# NOS_EEG_V2.net
KiCad netlist of a schematic drawn in Altium Designer
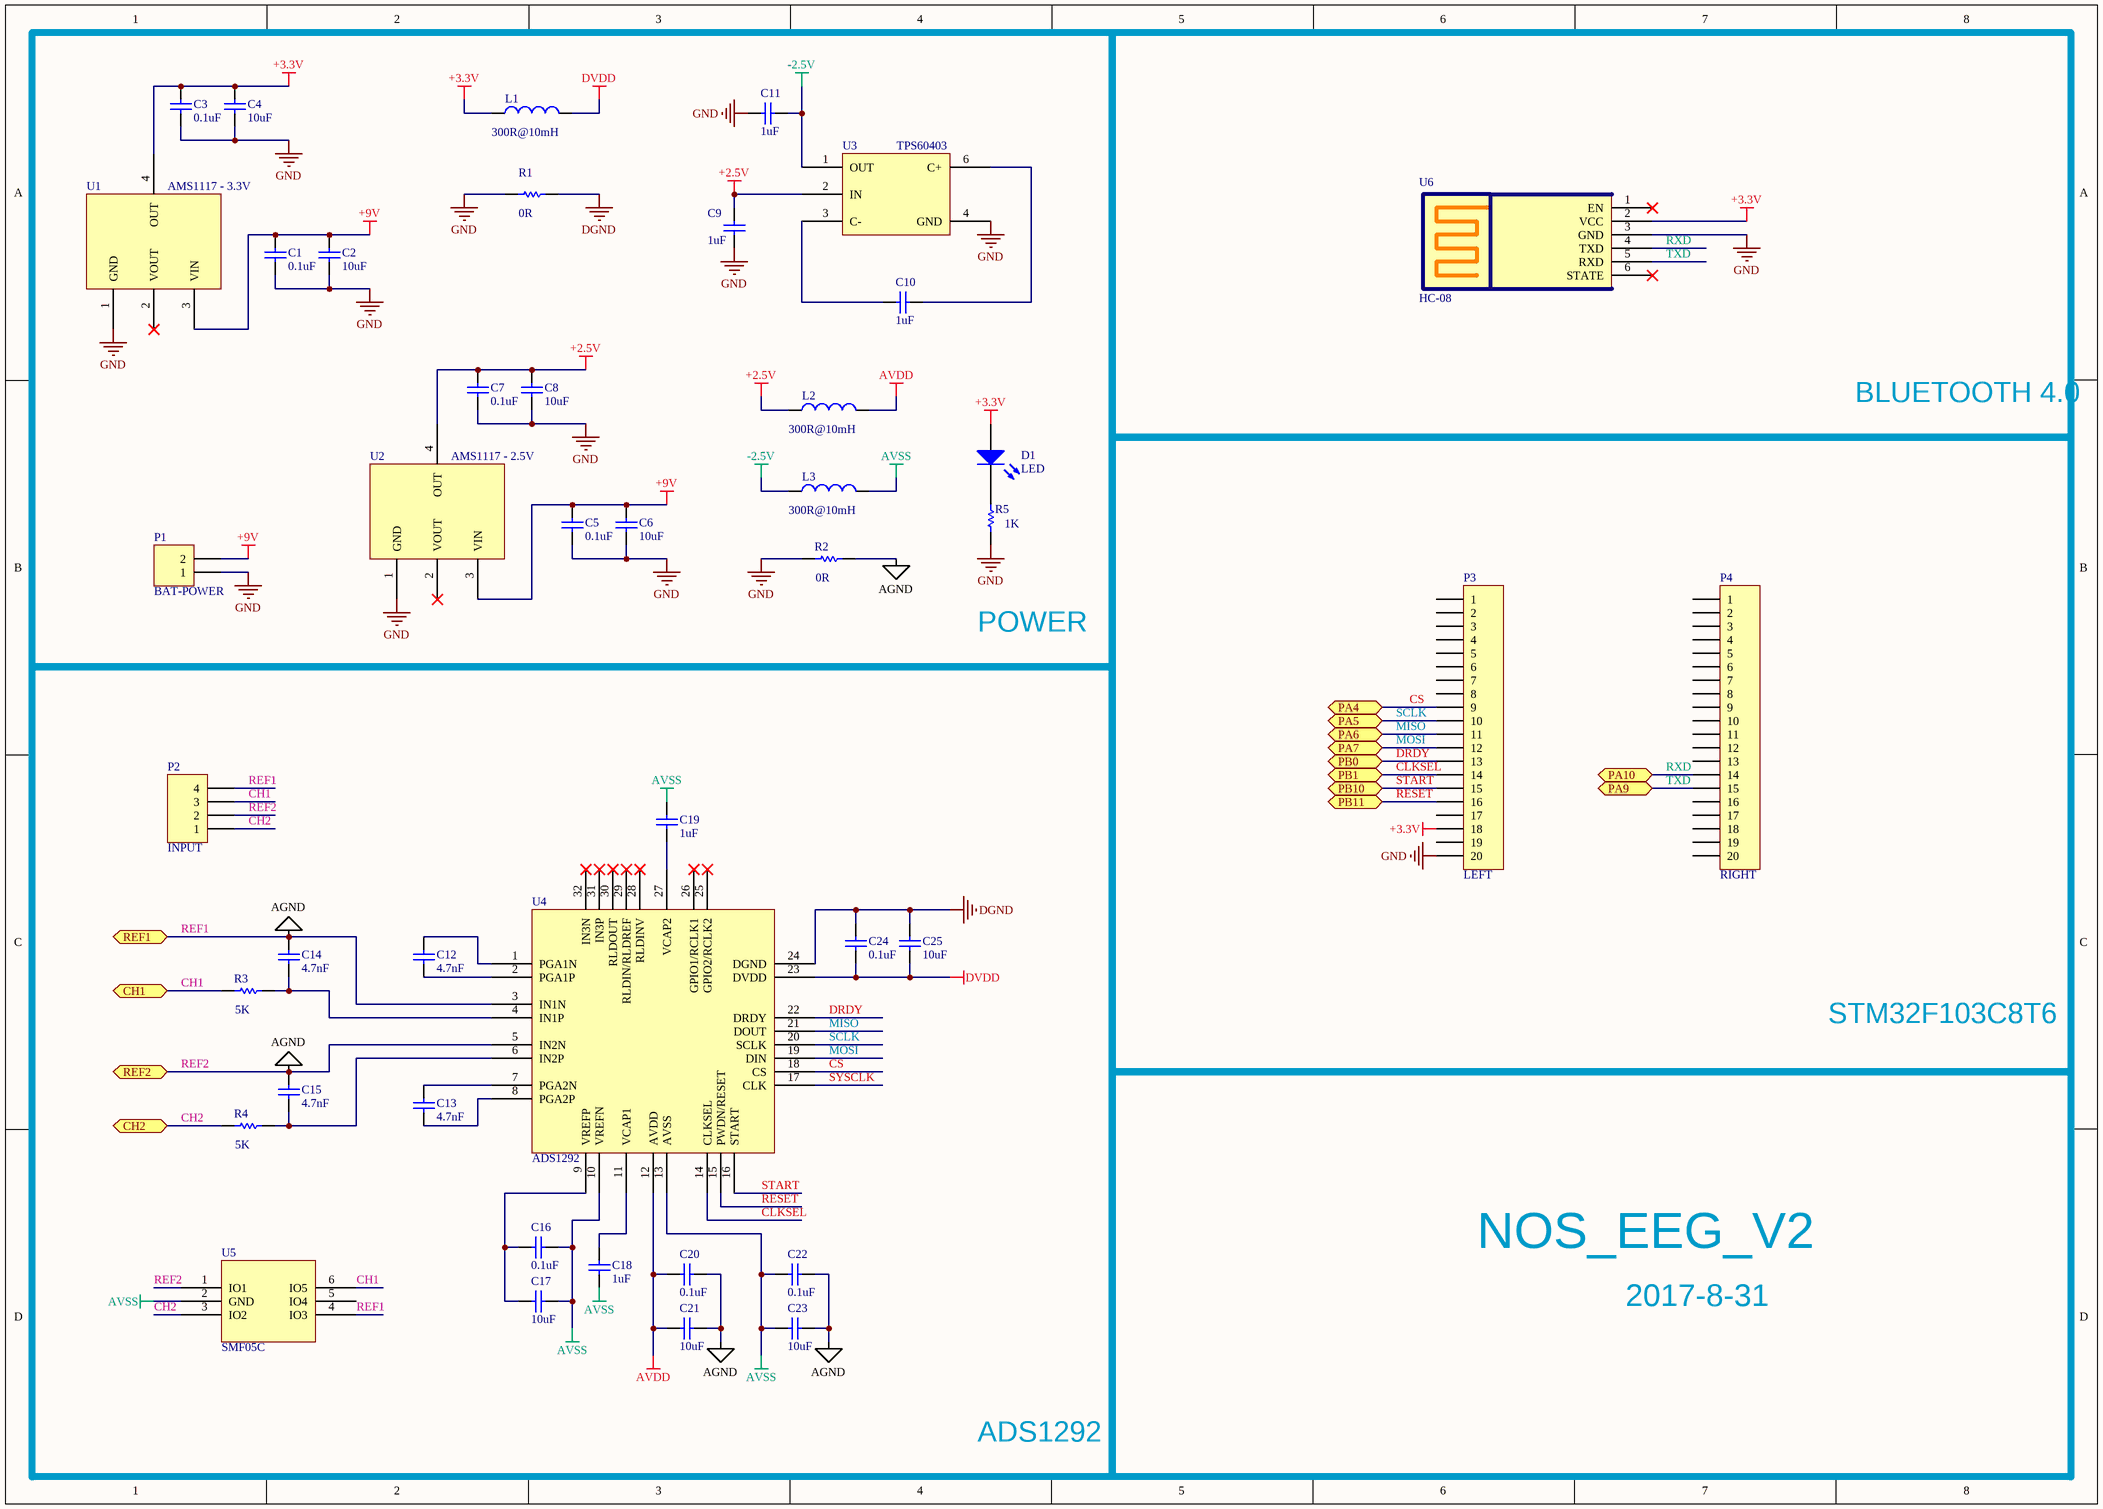
[diagram p0: NOS_EEG_V2.SchDoc]

(export (version "E")
  (design (tool "Eeschema 10.0.6"))
  (components
    (comp (ref "C1")
      (value "0.1uF")
      (footprint "0603")
      (description "Capacitor")
      (fields (field (name "Comment") "Cap") (field (name "PUBLISHER") "Altium Limited"))
      (libsource (lib "Miscellaneous Devices") (part "Cap"))
    )
    (comp (ref "C2")
      (value "10uF")
      (footprint "0603")
      (description "Capacitor")
      (fields (field (name "Comment") "Cap") (field (name "PUBLISHER") "Altium Limited"))
      (libsource (lib "Miscellaneous Devices") (part "Cap"))
    )
    (comp (ref "C3")
      (value "0.1uF")
      (footprint "0603")
      (description "Capacitor")
      (fields (field (name "Comment") "Cap") (field (name "PUBLISHER") "Altium Limited"))
      (libsource (lib "Miscellaneous Devices") (part "Cap"))
    )
    (comp (ref "C4")
      (value "10uF")
      (footprint "0603")
      (description "Capacitor")
      (fields (field (name "Comment") "Cap") (field (name "PUBLISHER") "Altium Limited"))
      (libsource (lib "Miscellaneous Devices") (part "Cap"))
    )
    (comp (ref "C5")
      (value "0.1uF")
      (footprint "0603")
      (description "Capacitor")
      (fields (field (name "Comment") "Cap") (field (name "PUBLISHER") "Altium Limited"))
      (libsource (lib "Miscellaneous Devices") (part "Cap"))
    )
    (comp (ref "C6")
      (value "10uF")
      (footprint "0603")
      (description "Capacitor")
      (fields (field (name "Comment") "Cap") (field (name "PUBLISHER") "Altium Limited"))
      (libsource (lib "Miscellaneous Devices") (part "Cap"))
    )
    (comp (ref "C7")
      (value "0.1uF")
      (footprint "0603")
      (description "Capacitor")
      (fields (field (name "Comment") "Cap") (field (name "PUBLISHER") "Altium Limited"))
      (libsource (lib "Miscellaneous Devices") (part "Cap"))
    )
    (comp (ref "C8")
      (value "10uF")
      (footprint "0603")
      (description "Capacitor")
      (fields (field (name "Comment") "Cap") (field (name "PUBLISHER") "Altium Limited"))
      (libsource (lib "Miscellaneous Devices") (part "Cap"))
    )
    (comp (ref "C9")
      (value "1uF")
      (footprint "0603")
      (description "Capacitor")
      (fields (field (name "Comment") "Cap") (field (name "PUBLISHER") "Altium Limited"))
      (libsource (lib "Miscellaneous Devices") (part "Cap"))
    )
    (comp (ref "C10")
      (value "1uF")
      (footprint "0603")
      (description "Capacitor")
      (fields (field (name "Comment") "Cap") (field (name "PUBLISHER") "Altium Limited"))
      (libsource (lib "Miscellaneous Devices") (part "Cap"))
    )
    (comp (ref "C11")
      (value "1uF")
      (footprint "0603")
      (description "Capacitor")
      (fields (field (name "Comment") "Cap") (field (name "PUBLISHER") "Altium Limited"))
      (libsource (lib "Miscellaneous Devices") (part "Cap"))
    )
    (comp (ref "C12")
      (value "4.7nF")
      (footprint "0603")
      (description "Capacitor")
      (fields (field (name "Comment") "Cap") (field (name "PUBLISHER") "Altium Limited"))
      (libsource (lib "Miscellaneous Devices") (part "Cap"))
    )
    (comp (ref "C13")
      (value "4.7nF")
      (footprint "0603")
      (description "Capacitor")
      (fields (field (name "Comment") "Cap") (field (name "PUBLISHER") "Altium Limited"))
      (libsource (lib "Miscellaneous Devices") (part "Cap"))
    )
    (comp (ref "C14")
      (value "4.7nF")
      (footprint "0603")
      (description "Capacitor")
      (fields (field (name "Comment") "Cap") (field (name "PUBLISHER") "Altium Limited"))
      (libsource (lib "Miscellaneous Devices") (part "Cap"))
    )
    (comp (ref "C15")
      (value "4.7nF")
      (footprint "0603")
      (description "Capacitor")
      (fields (field (name "Comment") "Cap") (field (name "PUBLISHER") "Altium Limited"))
      (libsource (lib "Miscellaneous Devices") (part "Cap"))
    )
    (comp (ref "C16")
      (value "0.1uF")
      (footprint "0603")
      (description "Capacitor")
      (fields (field (name "Comment") "Cap") (field (name "PUBLISHER") "Altium Limited"))
      (libsource (lib "Miscellaneous Devices") (part "Cap"))
    )
    (comp (ref "C17")
      (value "10uF")
      (footprint "0603")
      (description "Capacitor")
      (fields (field (name "Comment") "Cap") (field (name "PUBLISHER") "Altium Limited"))
      (libsource (lib "Miscellaneous Devices") (part "Cap"))
    )
    (comp (ref "C18")
      (value "1uF")
      (footprint "0603")
      (description "Capacitor")
      (fields (field (name "Comment") "Cap") (field (name "PUBLISHER") "Altium Limited"))
      (libsource (lib "Miscellaneous Devices") (part "Cap"))
    )
    (comp (ref "C19")
      (value "1uF")
      (footprint "0603")
      (description "Capacitor")
      (fields (field (name "Comment") "Cap") (field (name "PUBLISHER") "Altium Limited"))
      (libsource (lib "Miscellaneous Devices") (part "Cap"))
    )
    (comp (ref "C20")
      (value "0.1uF")
      (footprint "0603")
      (description "Capacitor")
      (fields (field (name "Comment") "Cap") (field (name "PUBLISHER") "Altium Limited"))
      (libsource (lib "Miscellaneous Devices") (part "Cap"))
    )
    (comp (ref "C21")
      (value "10uF")
      (footprint "0603")
      (description "Capacitor")
      (fields (field (name "Comment") "Cap") (field (name "PUBLISHER") "Altium Limited"))
      (libsource (lib "Miscellaneous Devices") (part "Cap"))
    )
    (comp (ref "C22")
      (value "0.1uF")
      (footprint "0603")
      (description "Capacitor")
      (fields (field (name "Comment") "Cap") (field (name "PUBLISHER") "Altium Limited"))
      (libsource (lib "Miscellaneous Devices") (part "Cap"))
    )
    (comp (ref "C23")
      (value "10uF")
      (footprint "0603")
      (description "Capacitor")
      (fields (field (name "Comment") "Cap") (field (name "PUBLISHER") "Altium Limited"))
      (libsource (lib "Miscellaneous Devices") (part "Cap"))
    )
    (comp (ref "C24")
      (value "0.1uF")
      (footprint "0603")
      (description "Capacitor")
      (fields (field (name "Comment") "Cap") (field (name "PUBLISHER") "Altium Limited"))
      (libsource (lib "Miscellaneous Devices") (part "Cap"))
    )
    (comp (ref "C25")
      (value "10uF")
      (footprint "0603")
      (description "Capacitor")
      (fields (field (name "Comment") "Cap") (field (name "PUBLISHER") "Altium Limited"))
      (libsource (lib "Miscellaneous Devices") (part "Cap"))
    )
    (comp (ref "D1")
      (value "LED")
      (footprint "0805")
      (description "Typical BLUE SiC LED")
      (fields (field (name "PUBLISHER") "Altium Limited"))
      (libsource (lib "NOS_EEG_V2") (part "LED3"))
    )
    (comp (ref "L1")
      (value "300R@10mH")
      (footprint "AXIAL0.4")
      (description "Inductor")
      (fields (field (name "PUBLISHER") "Altium Limited"))
      (libsource (lib "Miscellaneous Devices") (part "Inductor"))
    )
    (comp (ref "L2")
      (value "300R@10mH")
      (footprint "AXIAL0.4")
      (description "Inductor")
      (fields (field (name "PUBLISHER") "Altium Limited"))
      (libsource (lib "Miscellaneous Devices") (part "Inductor"))
    )
    (comp (ref "L3")
      (value "300R@10mH")
      (footprint "AXIAL0.4")
      (description "Inductor")
      (fields (field (name "PUBLISHER") "Altium Limited"))
      (libsource (lib "Miscellaneous Devices") (part "Inductor"))
    )
    (comp (ref "P1")
      (value "BAT-POWER")
      (footprint "HDR1X2")
      (description "Header, 2-Pin")
      (fields (field (name "PUBLISHER") "Altium Limited"))
      (libsource (lib "Miscellaneous Connectors") (part "Header 2"))
    )
    (comp (ref "P2")
      (value "INPUT")
      (footprint "HDR1X4")
      (description "Header, 4-Pin")
      (fields (field (name "PUBLISHER") "Altium Limited"))
      (libsource (lib "Miscellaneous Connectors") (part "Header 4"))
    )
    (comp (ref "P3")
      (value "LEFT")
      (footprint "HDR1X20")
      (description "Header, 20-Pin")
      (fields (field (name "PUBLISHER") "Altium Limited"))
      (libsource (lib "Miscellaneous Connectors") (part "Header 20"))
    )
    (comp (ref "P4")
      (value "RIGHT")
      (footprint "HDR1X20")
      (description "Header, 20-Pin")
      (fields (field (name "PUBLISHER") "Altium Limited"))
      (libsource (lib "Miscellaneous Connectors") (part "Header 20"))
    )
    (comp (ref "R1")
      (value "0R")
      (footprint "AXIAL-0.3")
      (description "Resistor")
      (fields (field (name "Comment") "Res1") (field (name "PUBLISHER") "Altium Limited"))
      (libsource (lib "Miscellaneous Devices") (part "Res1"))
    )
    (comp (ref "R2")
      (value "0R")
      (footprint "AXIAL-0.3")
      (description "Resistor")
      (fields (field (name "Comment") "Res1") (field (name "PUBLISHER") "Altium Limited"))
      (libsource (lib "Miscellaneous Devices") (part "Res1"))
    )
    (comp (ref "R3")
      (value "5K")
      (footprint "0603")
      (description "Resistor")
      (fields (field (name "Comment") "Res1") (field (name "PUBLISHER") "Altium Limited"))
      (libsource (lib "Miscellaneous Devices") (part "Res1"))
    )
    (comp (ref "R4")
      (value "5K")
      (footprint "0603")
      (description "Resistor")
      (fields (field (name "Comment") "Res1") (field (name "PUBLISHER") "Altium Limited"))
      (libsource (lib "Miscellaneous Devices") (part "Res1"))
    )
    (comp (ref "R5")
      (value "1K")
      (footprint "0603")
      (description "Resistor")
      (fields (field (name "Comment") "Res1") (field (name "PUBLISHER") "Altium Limited"))
      (libsource (lib "Miscellaneous Devices") (part "Res1"))
    )
    (comp (ref "U1")
      (value "AMS1117 - 3.3V")
      (footprint "SOT223")
      (description "AMS1117")
      (libsource (lib "NOS_EEG_V2") (part "AMS1117"))
    )
    (comp (ref "U2")
      (value "AMS1117 - 2.5V")
      (footprint "SOT223")
      (description "AMS1117")
      (libsource (lib "NOS_EEG_V2") (part "AMS1117"))
    )
    (comp (ref "U3")
      (value "TPS60403")
      (footprint "SOT23-5")
      (libsource (lib "NOS_EEG_V2") (part "TPS60403"))
    )
    (comp (ref "U4") (value "ADS1292") (footprint "PBS32_M") (libsource (lib "NOS_EEG_V2") (part "ADS1292")))
    (comp (ref "U5")
      (value "SMF05C")
      (footprint "INF-SOT363_V")
      (libsource (lib "NOS_EEG_V2") (part "SMF05C"))
    )
    (comp (ref "U6")
      (value "HC-08")
      (footprint "SIP6")
      (description "bluetooth")
      (libsource (lib "NOS_EEG_V1") (part "HC-05"))
    )
  )
  (nets
    (net (code "1") (name "+2.5V") (class "Default")
      (node (ref "C7") (pin "1") (pinfunction "1_1") (pintype "passive"))
      (node (ref "C8") (pin "1") (pinfunction "1_1") (pintype "passive"))
      (node (ref "C9") (pin "2") (pinfunction "2_2") (pintype "passive"))
      (node (ref "L2") (pin "1") (pinfunction "1_1") (pintype "passive"))
      (node (ref "U2") (pin "4") (pinfunction "OUT_4") (pintype "passive"))
      (node (ref "U3") (pin "2") (pinfunction "IN_2") (pintype "passive"))
    )
    (net (code "2") (name "+3.3V") (class "Default")
      (node (ref "C3") (pin "1") (pinfunction "1_1") (pintype "passive"))
      (node (ref "C4") (pin "1") (pinfunction "1_1") (pintype "passive"))
      (node (ref "D1") (pin "1") (pinfunction "A_1") (pintype "passive"))
      (node (ref "L1") (pin "1") (pinfunction "1_1") (pintype "passive"))
      (node (ref "P3") (pin "18") (pinfunction "18_18") (pintype "passive"))
      (node (ref "U1") (pin "4") (pinfunction "OUT_4") (pintype "passive"))
      (node (ref "U6") (pin "2") (pinfunction "VCC_2") (pintype "passive"))
    )
    (net (code "3") (name "+9V") (class "Default")
      (node (ref "C1") (pin "2") (pinfunction "2_2") (pintype "passive"))
      (node (ref "C2") (pin "2") (pinfunction "2_2") (pintype "passive"))
      (node (ref "C5") (pin "2") (pinfunction "2_2") (pintype "passive"))
      (node (ref "C6") (pin "2") (pinfunction "2_2") (pintype "passive"))
      (node (ref "P1") (pin "2") (pinfunction "2_2") (pintype "passive"))
      (node (ref "U1") (pin "3") (pinfunction "VIN_3") (pintype "passive"))
      (node (ref "U2") (pin "3") (pinfunction "VIN_3") (pintype "passive"))
    )
    (net (code "4") (name "-2.5V") (class "Default")
      (node (ref "C11") (pin "1") (pinfunction "1_1") (pintype "passive"))
      (node (ref "L3") (pin "1") (pinfunction "1_1") (pintype "passive"))
      (node (ref "U3") (pin "1") (pinfunction "OUT_1") (pintype "passive"))
    )
    (net (code "5") (name "/CH1") (class "Default")
      (node (ref "P2") (pin "3") (pinfunction "3_3") (pintype "passive"))
      (node (ref "R3") (pin "1") (pinfunction "1_1") (pintype "passive"))
      (node (ref "U5") (pin "6") (pinfunction "IO5_6") (pintype "passive"))
    )
    (net (code "6") (name "/CH2") (class "Default")
      (node (ref "P2") (pin "1") (pinfunction "1_1") (pintype "passive"))
      (node (ref "R4") (pin "1") (pinfunction "1_1") (pintype "passive"))
      (node (ref "U5") (pin "3") (pinfunction "IO2_3") (pintype "passive"))
    )
    (net (code "7") (name "/CLKSEL") (class "Default")
      (node (ref "P3") (pin "14") (pinfunction "14_14") (pintype "passive"))
      (node (ref "U4") (pin "14") (pinfunction "CLKSEL_14") (pintype "passive"))
    )
    (net (code "8") (name "/CS") (class "Default")
      (node (ref "P3") (pin "9") (pinfunction "9_9") (pintype "passive"))
      (node (ref "U4") (pin "18") (pinfunction "CS_18") (pintype "passive"))
    )
    (net (code "9") (name "/DRDY") (class "Default")
      (node (ref "P3") (pin "13") (pinfunction "13_13") (pintype "passive"))
      (node (ref "U4") (pin "22") (pinfunction "DRDY_22") (pintype "passive"))
    )
    (net (code "10") (name "/MISO") (class "Default")
      (node (ref "P3") (pin "11") (pinfunction "11_11") (pintype "passive"))
      (node (ref "U4") (pin "21") (pinfunction "DOUT_21") (pintype "passive"))
    )
    (net (code "11") (name "/MOSI") (class "Default")
      (node (ref "P3") (pin "12") (pinfunction "12_12") (pintype "passive"))
      (node (ref "U4") (pin "19") (pinfunction "DIN_19") (pintype "passive"))
    )
    (net (code "12") (name "/RESET") (class "Default")
      (node (ref "P3") (pin "16") (pinfunction "16_16") (pintype "passive"))
      (node (ref "U4") (pin "15") (pinfunction "PWDN/RESET_15") (pintype "passive"))
    )
    (net (code "13") (name "/RXD") (class "Default")
      (node (ref "P4") (pin "14") (pinfunction "14_14") (pintype "passive"))
      (node (ref "U6") (pin "4") (pinfunction "TXD_4") (pintype "passive"))
    )
    (net (code "14") (name "/SCLK") (class "Default")
      (node (ref "P3") (pin "10") (pinfunction "10_10") (pintype "passive"))
      (node (ref "U4") (pin "20") (pinfunction "SCLK_20") (pintype "passive"))
    )
    (net (code "15") (name "/START") (class "Default")
      (node (ref "P3") (pin "15") (pinfunction "15_15") (pintype "passive"))
      (node (ref "U4") (pin "16") (pinfunction "START_16") (pintype "passive"))
    )
    (net (code "16") (name "/SYSCLK") (class "Default")
      (node (ref "U4") (pin "17") (pinfunction "CLK_17") (pintype "passive"))
    )
    (net (code "17") (name "/TXD") (class "Default")
      (node (ref "P4") (pin "15") (pinfunction "15_15") (pintype "passive"))
      (node (ref "U6") (pin "5") (pinfunction "RXD_5") (pintype "passive"))
    )
    (net (code "18") (name "AGND") (class "Default")
      (node (ref "C14") (pin "2") (pinfunction "2_2") (pintype "passive"))
      (node (ref "C15") (pin "2") (pinfunction "2_2") (pintype "passive"))
      (node (ref "C20") (pin "1") (pinfunction "1_1") (pintype "passive"))
      (node (ref "C21") (pin "1") (pinfunction "1_1") (pintype "passive"))
      (node (ref "C22") (pin "1") (pinfunction "1_1") (pintype "passive"))
      (node (ref "C23") (pin "1") (pinfunction "1_1") (pintype "passive"))
      (node (ref "P2") (pin "2") (pinfunction "2_2") (pintype "passive"))
      (node (ref "P2") (pin "4") (pinfunction "4_4") (pintype "passive"))
      (node (ref "R2") (pin "2") (pinfunction "2_2") (pintype "passive"))
      (node (ref "U4") (pin "3") (pinfunction "IN1N_3") (pintype "passive"))
      (node (ref "U4") (pin "5") (pinfunction "IN2N_5") (pintype "passive"))
      (node (ref "U5") (pin "1") (pinfunction "IO1_1") (pintype "passive"))
      (node (ref "U5") (pin "4") (pinfunction "IO3_4") (pintype "passive"))
    )
    (net (code "19") (name "AVDD") (class "Default")
      (node (ref "C20") (pin "2") (pinfunction "2_2") (pintype "passive"))
      (node (ref "C21") (pin "2") (pinfunction "2_2") (pintype "passive"))
      (node (ref "L2") (pin "2") (pinfunction "2_2") (pintype "passive"))
      (node (ref "U4") (pin "12") (pinfunction "AVDD_12") (pintype "passive"))
    )
    (net (code "20") (name "AVSS") (class "Default")
      (node (ref "C16") (pin "1") (pinfunction "1_1") (pintype "passive"))
      (node (ref "C17") (pin "1") (pinfunction "1_1") (pintype "passive"))
      (node (ref "C18") (pin "2") (pinfunction "2_2") (pintype "passive"))
      (node (ref "C19") (pin "1") (pinfunction "1_1") (pintype "passive"))
      (node (ref "C22") (pin "2") (pinfunction "2_2") (pintype "passive"))
      (node (ref "C23") (pin "2") (pinfunction "2_2") (pintype "passive"))
      (node (ref "L3") (pin "2") (pinfunction "2_2") (pintype "passive"))
      (node (ref "U4") (pin "10") (pinfunction "VREFN_10") (pintype "passive"))
      (node (ref "U4") (pin "13") (pinfunction "AVSS_13") (pintype "passive"))
      (node (ref "U5") (pin "2") (pinfunction "GND_2") (pintype "passive"))
    )
    (net (code "21") (name "DGND") (class "Default")
      (node (ref "C24") (pin "1") (pinfunction "1_1") (pintype "passive"))
      (node (ref "C25") (pin "1") (pinfunction "1_1") (pintype "passive"))
      (node (ref "R1") (pin "2") (pinfunction "2_2") (pintype "passive"))
      (node (ref "U4") (pin "24") (pinfunction "DGND_24") (pintype "passive"))
    )
    (net (code "22") (name "DVDD") (class "Default")
      (node (ref "C24") (pin "2") (pinfunction "2_2") (pintype "passive"))
      (node (ref "C25") (pin "2") (pinfunction "2_2") (pintype "passive"))
      (node (ref "L1") (pin "2") (pinfunction "2_2") (pintype "passive"))
      (node (ref "U4") (pin "23") (pinfunction "DVDD_23") (pintype "passive"))
    )
    (net (code "23") (name "GND") (class "Default")
      (node (ref "C1") (pin "1") (pinfunction "1_1") (pintype "passive"))
      (node (ref "C11") (pin "2") (pinfunction "2_2") (pintype "passive"))
      (node (ref "C2") (pin "1") (pinfunction "1_1") (pintype "passive"))
      (node (ref "C3") (pin "2") (pinfunction "2_2") (pintype "passive"))
      (node (ref "C4") (pin "2") (pinfunction "2_2") (pintype "passive"))
      (node (ref "C5") (pin "1") (pinfunction "1_1") (pintype "passive"))
      (node (ref "C6") (pin "1") (pinfunction "1_1") (pintype "passive"))
      (node (ref "C7") (pin "2") (pinfunction "2_2") (pintype "passive"))
      (node (ref "C8") (pin "2") (pinfunction "2_2") (pintype "passive"))
      (node (ref "C9") (pin "1") (pinfunction "1_1") (pintype "passive"))
      (node (ref "P1") (pin "1") (pinfunction "1_1") (pintype "passive"))
      (node (ref "P3") (pin "20") (pinfunction "20_20") (pintype "passive"))
      (node (ref "R1") (pin "1") (pinfunction "1_1") (pintype "passive"))
      (node (ref "R2") (pin "1") (pinfunction "1_1") (pintype "passive"))
      (node (ref "R5") (pin "1") (pinfunction "1_1") (pintype "passive"))
      (node (ref "U1") (pin "1") (pinfunction "GND_1") (pintype "passive"))
      (node (ref "U2") (pin "1") (pinfunction "GND_1") (pintype "passive"))
      (node (ref "U3") (pin "4") (pinfunction "GND_4") (pintype "passive"))
      (node (ref "U6") (pin "3") (pinfunction "GND_3") (pintype "passive"))
    )
    (net (code "24") (name "Net-(D1-K)") (class "Default")
      (node (ref "D1") (pin "2") (pinfunction "K_2") (pintype "passive"))
      (node (ref "R5") (pin "2") (pinfunction "2_2") (pintype "passive"))
    )
    (net (code "25") (name "Net-(U3-C+)") (class "Default")
      (node (ref "C10") (pin "1") (pinfunction "1_1") (pintype "passive"))
      (node (ref "U3") (pin "6") (pinfunction "C+_6") (pintype "passive"))
    )
    (net (code "26") (name "Net-(U3-C-)") (class "Default")
      (node (ref "C10") (pin "2") (pinfunction "2_2") (pintype "passive"))
      (node (ref "U3") (pin "3") (pinfunction "C-_3") (pintype "passive"))
    )
    (net (code "27") (name "Net-(U4-IN1P)") (class "Default")
      (node (ref "C14") (pin "1") (pinfunction "1_1") (pintype "passive"))
      (node (ref "R3") (pin "2") (pinfunction "2_2") (pintype "passive"))
      (node (ref "U4") (pin "4") (pinfunction "IN1P_4") (pintype "passive"))
    )
    (net (code "28") (name "Net-(U4-IN2P)") (class "Default")
      (node (ref "C15") (pin "1") (pinfunction "1_1") (pintype "passive"))
      (node (ref "R4") (pin "2") (pinfunction "2_2") (pintype "passive"))
      (node (ref "U4") (pin "6") (pinfunction "IN2P_6") (pintype "passive"))
    )
    (net (code "29") (name "Net-(U4-PGA1N)") (class "Default")
      (node (ref "C12") (pin "2") (pinfunction "2_2") (pintype "passive"))
      (node (ref "U4") (pin "1") (pinfunction "PGA1N_1") (pintype "passive"))
    )
    (net (code "30") (name "Net-(U4-PGA1P)") (class "Default")
      (node (ref "C12") (pin "1") (pinfunction "1_1") (pintype "passive"))
      (node (ref "U4") (pin "2") (pinfunction "PGA1P_2") (pintype "passive"))
    )
    (net (code "31") (name "Net-(U4-PGA2N)") (class "Default")
      (node (ref "C13") (pin "1") (pinfunction "1_1") (pintype "passive"))
      (node (ref "U4") (pin "7") (pinfunction "PGA2N_7") (pintype "passive"))
    )
    (net (code "32") (name "Net-(U4-PGA2P)") (class "Default")
      (node (ref "C13") (pin "2") (pinfunction "2_2") (pintype "passive"))
      (node (ref "U4") (pin "8") (pinfunction "PGA2P_8") (pintype "passive"))
    )
    (net (code "33") (name "Net-(U4-VCAP1)") (class "Default")
      (node (ref "C18") (pin "1") (pinfunction "1_1") (pintype "passive"))
      (node (ref "U4") (pin "11") (pinfunction "VCAP1_11") (pintype "passive"))
    )
    (net (code "34") (name "Net-(U4-VCAP2)") (class "Default")
      (node (ref "C19") (pin "2") (pinfunction "2_2") (pintype "passive"))
      (node (ref "U4") (pin "27") (pinfunction "VCAP2_27") (pintype "passive"))
    )
    (net (code "35") (name "Net-(U4-VREFP)") (class "Default")
      (node (ref "C16") (pin "2") (pinfunction "2_2") (pintype "passive"))
      (node (ref "C17") (pin "2") (pinfunction "2_2") (pintype "passive"))
      (node (ref "U4") (pin "9") (pinfunction "VREFP_9") (pintype "passive"))
    )
    (net (code "36") (name "unconnected-(P3-Pad1)") (class "Default")
      (node (ref "P3") (pin "1") (pinfunction "1_1") (pintype "passive"))
    )
    (net (code "37") (name "unconnected-(P3-Pad2)") (class "Default")
      (node (ref "P3") (pin "2") (pinfunction "2_2") (pintype "passive"))
    )
    (net (code "38") (name "unconnected-(P3-Pad3)") (class "Default")
      (node (ref "P3") (pin "3") (pinfunction "3_3") (pintype "passive"))
    )
    (net (code "39") (name "unconnected-(P3-Pad4)") (class "Default")
      (node (ref "P3") (pin "4") (pinfunction "4_4") (pintype "passive"))
    )
    (net (code "40") (name "unconnected-(P3-Pad5)") (class "Default")
      (node (ref "P3") (pin "5") (pinfunction "5_5") (pintype "passive"))
    )
    (net (code "41") (name "unconnected-(P3-Pad6)") (class "Default")
      (node (ref "P3") (pin "6") (pinfunction "6_6") (pintype "passive"))
    )
    (net (code "42") (name "unconnected-(P3-Pad7)") (class "Default")
      (node (ref "P3") (pin "7") (pinfunction "7_7") (pintype "passive"))
    )
    (net (code "43") (name "unconnected-(P3-Pad8)") (class "Default")
      (node (ref "P3") (pin "8") (pinfunction "8_8") (pintype "passive"))
    )
    (net (code "44") (name "unconnected-(P3-Pad17)") (class "Default")
      (node (ref "P3") (pin "17") (pinfunction "17_17") (pintype "passive"))
    )
    (net (code "45") (name "unconnected-(P3-Pad19)") (class "Default")
      (node (ref "P3") (pin "19") (pinfunction "19_19") (pintype "passive"))
    )
    (net (code "46") (name "unconnected-(P4-Pad1)") (class "Default")
      (node (ref "P4") (pin "1") (pinfunction "1_1") (pintype "passive"))
    )
    (net (code "47") (name "unconnected-(P4-Pad2)") (class "Default")
      (node (ref "P4") (pin "2") (pinfunction "2_2") (pintype "passive"))
    )
    (net (code "48") (name "unconnected-(P4-Pad3)") (class "Default")
      (node (ref "P4") (pin "3") (pinfunction "3_3") (pintype "passive"))
    )
    (net (code "49") (name "unconnected-(P4-Pad4)") (class "Default")
      (node (ref "P4") (pin "4") (pinfunction "4_4") (pintype "passive"))
    )
    (net (code "50") (name "unconnected-(P4-Pad5)") (class "Default")
      (node (ref "P4") (pin "5") (pinfunction "5_5") (pintype "passive"))
    )
    (net (code "51") (name "unconnected-(P4-Pad6)") (class "Default")
      (node (ref "P4") (pin "6") (pinfunction "6_6") (pintype "passive"))
    )
    (net (code "52") (name "unconnected-(P4-Pad7)") (class "Default")
      (node (ref "P4") (pin "7") (pinfunction "7_7") (pintype "passive"))
    )
    (net (code "53") (name "unconnected-(P4-Pad8)") (class "Default")
      (node (ref "P4") (pin "8") (pinfunction "8_8") (pintype "passive"))
    )
    (net (code "54") (name "unconnected-(P4-Pad9)") (class "Default")
      (node (ref "P4") (pin "9") (pinfunction "9_9") (pintype "passive"))
    )
    (net (code "55") (name "unconnected-(P4-Pad10)") (class "Default")
      (node (ref "P4") (pin "10") (pinfunction "10_10") (pintype "passive"))
    )
    (net (code "56") (name "unconnected-(P4-Pad11)") (class "Default")
      (node (ref "P4") (pin "11") (pinfunction "11_11") (pintype "passive"))
    )
    (net (code "57") (name "unconnected-(P4-Pad12)") (class "Default")
      (node (ref "P4") (pin "12") (pinfunction "12_12") (pintype "passive"))
    )
    (net (code "58") (name "unconnected-(P4-Pad13)") (class "Default")
      (node (ref "P4") (pin "13") (pinfunction "13_13") (pintype "passive"))
    )
    (net (code "59") (name "unconnected-(P4-Pad16)") (class "Default")
      (node (ref "P4") (pin "16") (pinfunction "16_16") (pintype "passive"))
    )
    (net (code "60") (name "unconnected-(P4-Pad17)") (class "Default")
      (node (ref "P4") (pin "17") (pinfunction "17_17") (pintype "passive"))
    )
    (net (code "61") (name "unconnected-(P4-Pad18)") (class "Default")
      (node (ref "P4") (pin "18") (pinfunction "18_18") (pintype "passive"))
    )
    (net (code "62") (name "unconnected-(P4-Pad19)") (class "Default")
      (node (ref "P4") (pin "19") (pinfunction "19_19") (pintype "passive"))
    )
    (net (code "63") (name "unconnected-(P4-Pad20)") (class "Default")
      (node (ref "P4") (pin "20") (pinfunction "20_20") (pintype "passive"))
    )
    (net (code "64") (name "unconnected-(U1-VOUT-Pad2)") (class "Default")
      (node (ref "U1") (pin "2") (pinfunction "VOUT_2") (pintype "passive+no_connect"))
    )
    (net (code "65") (name "unconnected-(U2-VOUT-Pad2)") (class "Default")
      (node (ref "U2") (pin "2") (pinfunction "VOUT_2") (pintype "passive+no_connect"))
    )
    (net (code "66") (name "unconnected-(U4-GPIO1{slash}RCLK1-Pad26)") (class "Default")
      (node (ref "U4") (pin "26") (pinfunction "GPIO1/RCLK1_26") (pintype "passive+no_connect"))
    )
    (net (code "67") (name "unconnected-(U4-GPIO2{slash}RCLK2-Pad25)") (class "Default")
      (node (ref "U4") (pin "25") (pinfunction "GPIO2/RCLK2_25") (pintype "passive+no_connect"))
    )
    (net (code "68") (name "unconnected-(U4-IN3N-Pad32)") (class "Default")
      (node (ref "U4") (pin "32") (pinfunction "IN3N_32") (pintype "passive+no_connect"))
    )
    (net (code "69") (name "unconnected-(U4-IN3P-Pad31)") (class "Default")
      (node (ref "U4") (pin "31") (pinfunction "IN3P_31") (pintype "passive+no_connect"))
    )
    (net (code "70") (name "unconnected-(U4-RLDINV-Pad28)") (class "Default")
      (node (ref "U4") (pin "28") (pinfunction "RLDINV_28") (pintype "passive+no_connect"))
    )
    (net (code "71") (name "unconnected-(U4-RLDIN{slash}RLDREF-Pad29)") (class "Default")
      (node (ref "U4") (pin "29") (pinfunction "RLDIN/RLDREF_29") (pintype "passive+no_connect"))
    )
    (net (code "72") (name "unconnected-(U4-RLDOUT-Pad30)") (class "Default")
      (node (ref "U4") (pin "30") (pinfunction "RLDOUT_30") (pintype "passive+no_connect"))
    )
    (net (code "73") (name "unconnected-(U5-IO4-Pad5)") (class "Default")
      (node (ref "U5") (pin "5") (pinfunction "IO4_5") (pintype "passive"))
    )
    (net (code "74") (name "unconnected-(U6-EN-Pad1)") (class "Default")
      (node (ref "U6") (pin "1") (pinfunction "EN_1") (pintype "passive+no_connect"))
    )
    (net (code "75") (name "unconnected-(U6-STATE-Pad6)") (class "Default")
      (node (ref "U6") (pin "6") (pinfunction "STATE_6") (pintype "passive+no_connect"))
    )
  )
)
